# power.net
KiCad netlist of a schematic drawn in Altium Designer
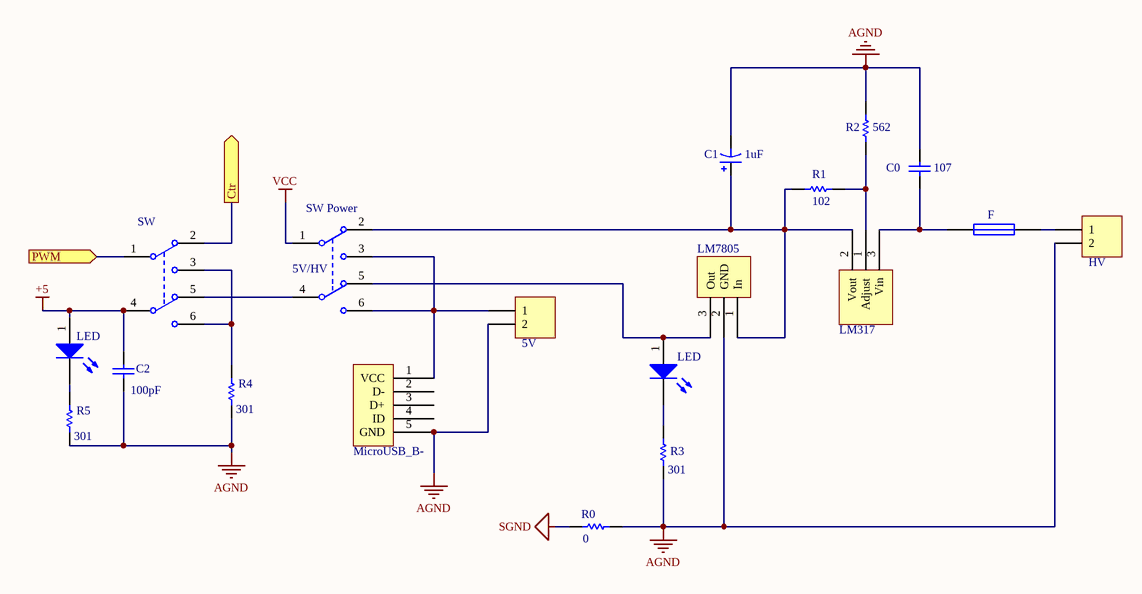
[diagram p0: power.SchDoc]

(export (version "E")
  (design (tool "Eeschema 10.0.6"))
  (components
    (comp (ref "C0")
      (value "107")
      (footprint "0805(M)")
      (description "非极性电容")
      (fields (field (name "Comment") "Cap2"))
      (libsource (lib "Self Establish") (part "Cap2"))
    )
    (comp (ref "C1")
      (value "1uF")
      (footprint "25V47uF(DIP)")
      (description "极性电容")
      (fields (field (name "Comment") "Cap1"))
      (libsource (lib "Self Establish") (part "Cap1"))
    )
    (comp (ref "C2")
      (value "100pF")
      (footprint "0805(M)")
      (description "非极性电容")
      (fields (field (name "Comment") "Cap2"))
      (libsource (lib "Self Establish") (part "Cap2"))
    )
    (comp (ref "F")
      (value "Fuse")
      (footprint "1812(M)")
      (description "保险丝")
      (libsource (lib "Self Establish") (part "Fuse"))
    )
    (comp (ref "LED0") (value "LED") (footprint "0805_(M)") (libsource (lib "Self Establish") (part "LED")))
    (comp (ref "LED1") (value "LED") (footprint "0805_(M)") (libsource (lib "Self Establish") (part "LED")))
    (comp (ref "LM0")
      (value "LM317")
      (footprint "TO220(DIP)")
      (description "三端稳压(可调)")
      (libsource (lib "Self Establish") (part "LM317*"))
    )
    (comp (ref "LM1")
      (value "LM7805")
      (footprint "TO220(DIP)")
      (description "三端稳压")
      (libsource (lib "Self Establish") (part "LM7805*"))
    )
    (comp (ref "R0")
      (value "0")
      (footprint "0805(M)")
      (fields (field (name "Comment") "Res"))
      (libsource (lib "Self Establish") (part "Res"))
    )
    (comp (ref "R1")
      (value "102")
      (footprint "0805(M)")
      (fields (field (name "Comment") "Res"))
      (libsource (lib "Self Establish") (part "Res"))
    )
    (comp (ref "R2")
      (value "562")
      (footprint "0805(M)")
      (fields (field (name "Comment") "Res"))
      (libsource (lib "Self Establish") (part "Res"))
    )
    (comp (ref "R3")
      (value "301")
      (footprint "0805(M)")
      (fields (field (name "Comment") "Res"))
      (libsource (lib "Self Establish") (part "Res"))
    )
    (comp (ref "R4")
      (value "301")
      (footprint "0805(M)")
      (fields (field (name "Comment") "Res"))
      (libsource (lib "Self Establish") (part "Res"))
    )
    (comp (ref "R5")
      (value "301")
      (footprint "0805(M)")
      (fields (field (name "Comment") "Res"))
      (libsource (lib "Self Establish") (part "Res"))
    )
    (comp (ref "SW")
      (value "AFT-03(8*8)")
      (footprint "AFT-03(DIP)")
      (description "双刀双掷(DPDT)")
      (libsource (lib "Self Establish") (part "AFT-03(8*8)"))
    )
    (comp (ref "SW Power")
      (value "AFT-03(8*8)")
      (footprint "AFT-03(DIP)")
      (description "双刀双掷(DPDT)")
      (libsource (lib "Self Establish") (part "AFT-03(8*8)"))
    )
    (comp (ref "Ter2P0")
      (value "HV")
      (footprint "KF301-2P(DIP)")
      (description "接线端子 脚距5.08MM 300V/16A")
      (libsource (lib "Self Establish") (part "KF301-2P"))
    )
    (comp (ref "Ter2P1")
      (value "5V")
      (footprint "KF301-2P(DIP)")
      (description "接线端子 脚距5.08MM 300V/16A")
      (libsource (lib "Self Establish") (part "KF301-2P"))
    )
    (comp (ref "USB0")
      (value "MicroUSB_B-")
      (footprint "MicroUSB_B-(M)")
      (description "母头")
      (libsource (lib "Self Establish") (part "MicroUSB_B-"))
    )
  )
  (nets
    (net (code "1") (name "+5") (class "Default")
      (node (ref "C2") (pin "2") (pinfunction "2_2") (pintype "passive"))
      (node (ref "LED1") (pin "1") (pinfunction "P_1") (pintype "passive"))
      (node (ref "SW") (pin "4") (pinfunction "COMMON2_4") (pintype "passive"))
    )
    (net (code "2") (name "/Ctr") (class "Default")
      (node (ref "SW") (pin "2") (pinfunction "NC1_2") (pintype "passive"))
    )
    (net (code "3") (name "/PWM") (class "Default")
      (node (ref "SW") (pin "1") (pinfunction "COMMON1_1") (pintype "passive"))
    )
    (net (code "4") (name "AGND") (class "Default")
      (node (ref "C0") (pin "1") (pinfunction "1_1") (pintype "passive"))
      (node (ref "C1") (pin "2") (pinfunction "2_2") (pintype "passive"))
      (node (ref "C2") (pin "1") (pinfunction "1_1") (pintype "passive"))
      (node (ref "LM1") (pin "2") (pinfunction "GND_2") (pintype "power_in"))
      (node (ref "R0") (pin "2") (pinfunction "2_2") (pintype "passive"))
      (node (ref "R2") (pin "2") (pinfunction "2_2") (pintype "passive"))
      (node (ref "R3") (pin "2") (pinfunction "2_2") (pintype "passive"))
      (node (ref "R4") (pin "2") (pinfunction "2_2") (pintype "passive"))
      (node (ref "R5") (pin "2") (pinfunction "2_2") (pintype "passive"))
      (node (ref "Ter2P0") (pin "2") (pinfunction "2_2") (pintype "passive"))
      (node (ref "Ter2P1") (pin "2") (pinfunction "2_2") (pintype "passive"))
      (node (ref "USB0") (pin "5") (pinfunction "GND_5") (pintype "power_in"))
    )
    (net (code "5") (name "Net-(F-Pad2)") (class "Default")
      (node (ref "F") (pin "2") (pinfunction "2_2") (pintype "passive"))
      (node (ref "Ter2P0") (pin "1") (pinfunction "1_1") (pintype "passive"))
    )
    (net (code "6") (name "Net-(LED0-N)") (class "Default")
      (node (ref "LED0") (pin "2") (pinfunction "N_2") (pintype "passive"))
      (node (ref "R3") (pin "1") (pinfunction "1_1") (pintype "passive"))
    )
    (net (code "7") (name "Net-(LED0-P)") (class "Default")
      (node (ref "LED0") (pin "1") (pinfunction "P_1") (pintype "passive"))
      (node (ref "LM1") (pin "3") (pinfunction "Out_3") (pintype "passive"))
      (node (ref "SW Power") (pin "5") (pinfunction "NC2_5") (pintype "passive"))
    )
    (net (code "8") (name "Net-(LED1-N)") (class "Default")
      (node (ref "LED1") (pin "2") (pinfunction "N_2") (pintype "passive"))
      (node (ref "R5") (pin "1") (pinfunction "1_1") (pintype "passive"))
    )
    (net (code "9") (name "Net-(LM0-Adjust)") (class "Default")
      (node (ref "LM0") (pin "1") (pinfunction "Adjust_1") (pintype "passive"))
      (node (ref "R1") (pin "1") (pinfunction "1_1") (pintype "passive"))
      (node (ref "R2") (pin "1") (pinfunction "1_1") (pintype "passive"))
    )
    (net (code "10") (name "Net-(LM0-Vin)") (class "Default")
      (node (ref "C0") (pin "2") (pinfunction "2_2") (pintype "passive"))
      (node (ref "F") (pin "1") (pinfunction "1_1") (pintype "passive"))
      (node (ref "LM0") (pin "3") (pinfunction "Vin_3") (pintype "passive"))
    )
    (net (code "11") (name "Net-(LM0-Vout)") (class "Default")
      (node (ref "C1") (pin "1") (pinfunction "1_1") (pintype "passive"))
      (node (ref "LM0") (pin "2") (pinfunction "Vout_2") (pintype "passive"))
      (node (ref "LM1") (pin "1") (pinfunction "In_1") (pintype "passive"))
      (node (ref "R1") (pin "2") (pinfunction "2_2") (pintype "passive"))
      (node (ref "SW Power") (pin "2") (pinfunction "NC1_2") (pintype "passive"))
    )
    (net (code "12") (name "Net-(SW Power-COMMON2)") (class "Default")
      (node (ref "SW") (pin "5") (pinfunction "NC2_5") (pintype "passive"))
      (node (ref "SW Power") (pin "4") (pinfunction "COMMON2_4") (pintype "passive"))
    )
    (net (code "13") (name "Net-(SW Power-NO1)") (class "Default")
      (node (ref "SW Power") (pin "3") (pinfunction "NO1_3") (pintype "passive"))
      (node (ref "SW Power") (pin "6") (pinfunction "NO2_6") (pintype "passive"))
      (node (ref "Ter2P1") (pin "1") (pinfunction "1_1") (pintype "passive"))
      (node (ref "USB0") (pin "1") (pinfunction "VCC_1") (pintype "power_in"))
    )
    (net (code "14") (name "Net-(SW-NO1)") (class "Default")
      (node (ref "R4") (pin "1") (pinfunction "1_1") (pintype "passive"))
      (node (ref "SW") (pin "3") (pinfunction "NO1_3") (pintype "passive"))
      (node (ref "SW") (pin "6") (pinfunction "NO2_6") (pintype "passive"))
    )
    (net (code "15") (name "SGND") (class "Default")
      (node (ref "R0") (pin "1") (pinfunction "1_1") (pintype "passive"))
    )
    (net (code "16") (name "VCC") (class "Default")
      (node (ref "SW Power") (pin "1") (pinfunction "COMMON1_1") (pintype "passive"))
    )
    (net (code "17") (name "unconnected-(USB0-D+-Pad3)") (class "Default")
      (node (ref "USB0") (pin "3") (pinfunction "D+_3") (pintype "passive"))
    )
    (net (code "18") (name "unconnected-(USB0-D--Pad2)") (class "Default")
      (node (ref "USB0") (pin "2") (pinfunction "D-_2") (pintype "passive"))
    )
    (net (code "19") (name "unconnected-(USB0-ID-Pad4)") (class "Default")
      (node (ref "USB0") (pin "4") (pinfunction "ID_4") (pintype "passive"))
    )
  )
)
